# 01_-SensorAndActuator.net
KiCad netlist of a schematic drawn in Altium Designer
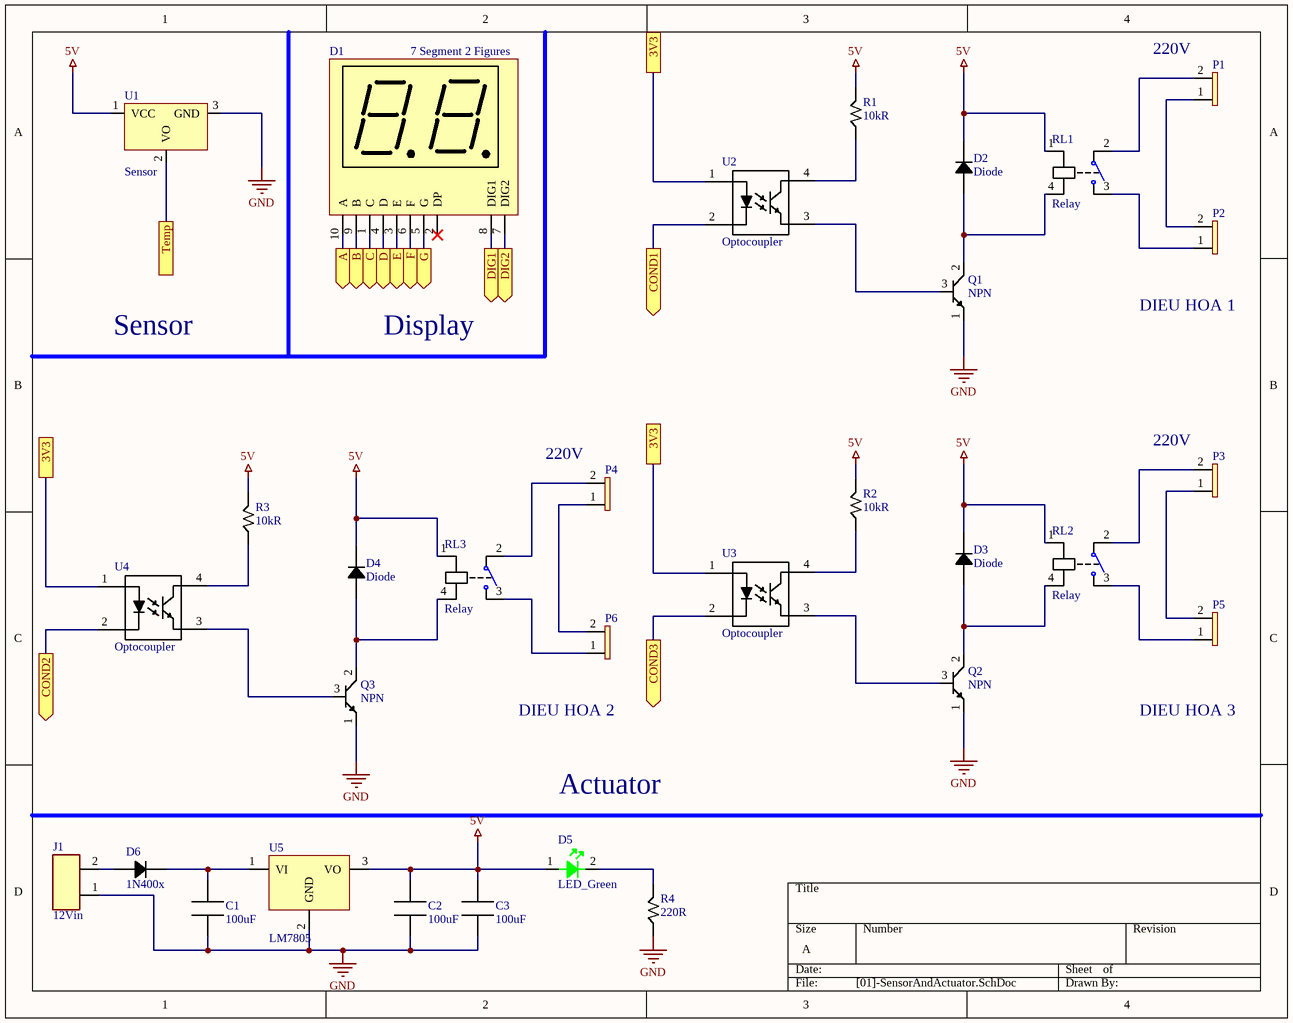
[diagram p0: [01]-SensorAndActuator.SchDoc]

(export (version "E")
  (design (tool "Eeschema 10.0.6"))
  (components
    (comp (ref "C1")
      (value "100uF")
      (footprint "Altium Lib:CAPC0805")
      (description "Capacitor_Non_Polar")
      (libsource (lib "Altium Lib") (part "Capacitor Non Polar"))
    )
    (comp (ref "C2")
      (value "100uF")
      (footprint "Altium Lib:CAPC0805")
      (description "Capacitor_Non_Polar")
      (libsource (lib "Altium Lib") (part "Capacitor Non Polar"))
    )
    (comp (ref "C3")
      (value "100uF")
      (footprint "Altium Lib:CAPC0805")
      (description "Capacitor_Non_Polar")
      (libsource (lib "Altium Lib") (part "Capacitor Non Polar"))
    )
    (comp (ref "D1")
      (value "7 Segment 2 Figures")
      (footprint "Altium Lib:5621BS")
      (libsource (lib "Altium Lib") (part "7 Segment 2 Figures"))
    )
    (comp (ref "D2")
      (value "Diode")
      (footprint "10A10")
      (description "Diode 10A")
      (libsource (lib "Altium Lib") (part "10A10"))
    )
    (comp (ref "D3")
      (value "Diode")
      (footprint "10A10")
      (description "Diode 10A")
      (libsource (lib "Altium Lib") (part "10A10"))
    )
    (comp (ref "D4")
      (value "Diode")
      (footprint "10A10")
      (description "Diode 10A")
      (libsource (lib "Altium Lib") (part "10A10"))
    )
    (comp (ref "D5")
      (value "LED_Green")
      (footprint "LED SMD 0805")
      (libsource (lib "Altium Lib") (part "LED_Green"))
    )
    (comp (ref "D6")
      (value "1N400x")
      (footprint "Altium Lib:1N400x")
      (description "1A - 1kV")
      (libsource (lib "Altium Lib") (part "Diode 1N4007"))
    )
    (comp (ref "J1")
      (value "12Vin")
      (footprint "Altium Lib:domino_2_pin")
      (description "2 Pins, 5.08mm")
      (libsource (lib "Altium Lib") (part "Domino 2 Pin"))
    )
    (comp (ref "P1")
      (value "Header 1*2 Pins")
      (footprint "HDR_M_2_PINS_2.54")
      (libsource (lib "Altium Lib") (part "Header 1x2 Pins"))
    )
    (comp (ref "P2")
      (value "Header 1*2 Pins")
      (footprint "HDR_M_2_PINS_2.54")
      (libsource (lib "Altium Lib") (part "Header 1x2 Pins"))
    )
    (comp (ref "P3")
      (value "Header 1*2 Pins")
      (footprint "HDR_M_2_PINS_2.54")
      (libsource (lib "Altium Lib") (part "Header 1x2 Pins"))
    )
    (comp (ref "P4")
      (value "Header 1*2 Pins")
      (footprint "HDR_M_2_PINS_2.54")
      (libsource (lib "Altium Lib") (part "Header 1x2 Pins"))
    )
    (comp (ref "P5")
      (value "Header 1*2 Pins")
      (footprint "HDR_M_2_PINS_2.54")
      (libsource (lib "Altium Lib") (part "Header 1x2 Pins"))
    )
    (comp (ref "P6")
      (value "Header 1*2 Pins")
      (footprint "HDR_M_2_PINS_2.54")
      (libsource (lib "Altium Lib") (part "Header 1x2 Pins"))
    )
    (comp (ref "Q1")
      (value "NPN")
      (footprint "to-92")
      (description "Transistor NPN")
      (libsource (lib "Altium Lib") (part "2SC1815"))
    )
    (comp (ref "Q2")
      (value "NPN")
      (footprint "to-92")
      (description "Transistor NPN")
      (libsource (lib "Altium Lib") (part "2SC1815"))
    )
    (comp (ref "Q3")
      (value "NPN")
      (footprint "to-92")
      (description "Transistor NPN")
      (libsource (lib "Altium Lib") (part "2SC1815"))
    )
    (comp (ref "R1")
      (value "10kR")
      (footprint "Altium Lib:RESC0805")
      (description "Resistor_TH_1/4W")
      (libsource (lib "Altium Lib") (part "Resistor"))
    )
    (comp (ref "R2")
      (value "10kR")
      (footprint "Altium Lib:RESC0805")
      (description "Resistor_TH_1/4W")
      (libsource (lib "Altium Lib") (part "Resistor"))
    )
    (comp (ref "R3")
      (value "10kR")
      (footprint "Altium Lib:RESC0805")
      (description "Resistor_TH_1/4W")
      (libsource (lib "Altium Lib") (part "Resistor"))
    )
    (comp (ref "R4")
      (value "220R")
      (footprint "Altium Lib:RESC0805")
      (description "Resistor_TH_1/4W")
      (libsource (lib "Altium Lib") (part "Resistor"))
    )
    (comp (ref "RL1")
      (value "Relay")
      (footprint "Relay G5NB")
      (description "4 Pins")
      (libsource (lib "Altium Lib") (part "Relay G5NB"))
    )
    (comp (ref "RL2")
      (value "Relay")
      (footprint "Relay G5NB")
      (description "4 Pins")
      (libsource (lib "Altium Lib") (part "Relay G5NB"))
    )
    (comp (ref "RL3")
      (value "Relay")
      (footprint "Relay G5NB")
      (description "4 Pins")
      (libsource (lib "Altium Lib") (part "Relay G5NB"))
    )
    (comp (ref "U1")
      (value "Sensor")
      (footprint "to-92")
      (description "Temperature sensor")
      (libsource (lib "Altium Lib") (part "LM35"))
    )
    (comp (ref "U2")
      (value "Optocoupler")
      (footprint "DIP 4")
      (description "Opto")
      (libsource (lib "Altium Lib") (part "Optocoupler"))
    )
    (comp (ref "U3")
      (value "Optocoupler")
      (footprint "DIP 4")
      (description "Opto")
      (libsource (lib "Altium Lib") (part "Optocoupler"))
    )
    (comp (ref "U4")
      (value "Optocoupler")
      (footprint "DIP 4")
      (description "Opto")
      (libsource (lib "Altium Lib") (part "Optocoupler"))
    )
    (comp (ref "U5")
      (value "LM7805")
      (footprint "Altium Lib:LM7805")
      (description "5V, 1A")
      (libsource (lib "Altium Lib") (part "LM7805"))
    )
  )
  (nets
    (net (code "1") (name "/3V3") (class "Default")
      (node (ref "U2") (pin "1") (pinfunction "Anode_1") (pintype "passive"))
      (node (ref "U3") (pin "1") (pinfunction "Anode_1") (pintype "passive"))
      (node (ref "U4") (pin "1") (pinfunction "Anode_1") (pintype "passive"))
    )
    (net (code "2") (name "/A") (class "Default")
      (node (ref "D1") (pin "10") (pinfunction "A_10") (pintype "passive"))
    )
    (net (code "3") (name "/B") (class "Default")
      (node (ref "D1") (pin "9") (pinfunction "B_9") (pintype "passive"))
    )
    (net (code "4") (name "/C") (class "Default")
      (node (ref "D1") (pin "1") (pinfunction "C_1") (pintype "passive"))
    )
    (net (code "5") (name "/COND1") (class "Default")
      (node (ref "U2") (pin "2") (pinfunction "Cathode_2") (pintype "passive"))
    )
    (net (code "6") (name "/COND2") (class "Default")
      (node (ref "U4") (pin "2") (pinfunction "Cathode_2") (pintype "passive"))
    )
    (net (code "7") (name "/COND3") (class "Default")
      (node (ref "U3") (pin "2") (pinfunction "Cathode_2") (pintype "passive"))
    )
    (net (code "8") (name "/D") (class "Default")
      (node (ref "D1") (pin "4") (pinfunction "D_4") (pintype "passive"))
    )
    (net (code "9") (name "/DIG1") (class "Default")
      (node (ref "D1") (pin "8") (pinfunction "DIG1_8") (pintype "passive"))
    )
    (net (code "10") (name "/DIG2") (class "Default")
      (node (ref "D1") (pin "7") (pinfunction "DIG2_7") (pintype "passive"))
    )
    (net (code "11") (name "/E") (class "Default")
      (node (ref "D1") (pin "3") (pinfunction "E_3") (pintype "passive"))
    )
    (net (code "12") (name "/F") (class "Default")
      (node (ref "D1") (pin "6") (pinfunction "F_6") (pintype "passive"))
    )
    (net (code "13") (name "/G") (class "Default")
      (node (ref "D1") (pin "5") (pinfunction "G_5") (pintype "passive"))
    )
    (net (code "14") (name "/Temp") (class "Default")
      (node (ref "U1") (pin "2") (pinfunction "VO_2") (pintype "passive"))
    )
    (net (code "15") (name "5V") (class "Default")
      (node (ref "C2") (pin "2") (pinfunction "2_2") (pintype "passive"))
      (node (ref "C3") (pin "2") (pinfunction "2_2") (pintype "passive"))
      (node (ref "D2") (pin "2") (pinfunction "2_2") (pintype "passive"))
      (node (ref "D3") (pin "2") (pinfunction "2_2") (pintype "passive"))
      (node (ref "D4") (pin "2") (pinfunction "2_2") (pintype "passive"))
      (node (ref "D5") (pin "1") (pinfunction "1_1") (pintype "passive"))
      (node (ref "R1") (pin "2") (pinfunction "2_2") (pintype "passive"))
      (node (ref "R2") (pin "2") (pinfunction "2_2") (pintype "passive"))
      (node (ref "R3") (pin "2") (pinfunction "2_2") (pintype "passive"))
      (node (ref "RL1") (pin "1") (pinfunction "1_1") (pintype "passive"))
      (node (ref "RL2") (pin "1") (pinfunction "1_1") (pintype "passive"))
      (node (ref "RL3") (pin "1") (pinfunction "1_1") (pintype "passive"))
      (node (ref "U1") (pin "1") (pinfunction "VCC_1") (pintype "passive"))
      (node (ref "U5") (pin "3") (pinfunction "VO_3") (pintype "passive"))
    )
    (net (code "16") (name "GND") (class "Default")
      (node (ref "C1") (pin "1") (pinfunction "1_1") (pintype "passive"))
      (node (ref "C2") (pin "1") (pinfunction "1_1") (pintype "passive"))
      (node (ref "C3") (pin "1") (pinfunction "1_1") (pintype "passive"))
      (node (ref "J1") (pin "1") (pinfunction "1_1") (pintype "passive"))
      (node (ref "Q1") (pin "1") (pinfunction "Emitter_1") (pintype "passive"))
      (node (ref "Q2") (pin "1") (pinfunction "Emitter_1") (pintype "passive"))
      (node (ref "Q3") (pin "1") (pinfunction "Emitter_1") (pintype "passive"))
      (node (ref "R4") (pin "1") (pinfunction "1_1") (pintype "passive"))
      (node (ref "U1") (pin "3") (pinfunction "GND_3") (pintype "passive"))
      (node (ref "U5") (pin "2") (pinfunction "GND_2") (pintype "passive"))
    )
    (net (code "17") (name "Net-(D5-Pad2)") (class "Default")
      (node (ref "D5") (pin "2") (pinfunction "2_2") (pintype "passive"))
      (node (ref "R4") (pin "2") (pinfunction "2_2") (pintype "passive"))
    )
    (net (code "18") (name "Net-(D6-Pad1)") (class "Default")
      (node (ref "D6") (pin "1") (pinfunction "1_1") (pintype "passive"))
      (node (ref "J1") (pin "2") (pinfunction "2_2") (pintype "passive"))
    )
    (net (code "19") (name "Net-(P1-Pad1)") (class "Default")
      (node (ref "P1") (pin "1") (pinfunction "1_1") (pintype "passive"))
      (node (ref "P2") (pin "2") (pinfunction "2_2") (pintype "passive"))
    )
    (net (code "20") (name "Net-(P1-Pad2)") (class "Default")
      (node (ref "P1") (pin "2") (pinfunction "2_2") (pintype "passive"))
      (node (ref "RL1") (pin "2") (pinfunction "2_2") (pintype "passive"))
    )
    (net (code "21") (name "Net-(P2-Pad1)") (class "Default")
      (node (ref "P2") (pin "1") (pinfunction "1_1") (pintype "passive"))
      (node (ref "RL1") (pin "3") (pinfunction "3_3") (pintype "passive"))
    )
    (net (code "22") (name "Net-(P3-Pad1)") (class "Default")
      (node (ref "P3") (pin "1") (pinfunction "1_1") (pintype "passive"))
      (node (ref "P5") (pin "2") (pinfunction "2_2") (pintype "passive"))
    )
    (net (code "23") (name "Net-(P3-Pad2)") (class "Default")
      (node (ref "P3") (pin "2") (pinfunction "2_2") (pintype "passive"))
      (node (ref "RL2") (pin "2") (pinfunction "2_2") (pintype "passive"))
    )
    (net (code "24") (name "Net-(P4-Pad1)") (class "Default")
      (node (ref "P4") (pin "1") (pinfunction "1_1") (pintype "passive"))
      (node (ref "P6") (pin "2") (pinfunction "2_2") (pintype "passive"))
    )
    (net (code "25") (name "Net-(P4-Pad2)") (class "Default")
      (node (ref "P4") (pin "2") (pinfunction "2_2") (pintype "passive"))
      (node (ref "RL3") (pin "2") (pinfunction "2_2") (pintype "passive"))
    )
    (net (code "26") (name "Net-(P5-Pad1)") (class "Default")
      (node (ref "P5") (pin "1") (pinfunction "1_1") (pintype "passive"))
      (node (ref "RL2") (pin "3") (pinfunction "3_3") (pintype "passive"))
    )
    (net (code "27") (name "Net-(P6-Pad1)") (class "Default")
      (node (ref "P6") (pin "1") (pinfunction "1_1") (pintype "passive"))
      (node (ref "RL3") (pin "3") (pinfunction "3_3") (pintype "passive"))
    )
    (net (code "28") (name "Net-(Q1-Base)") (class "Default")
      (node (ref "Q1") (pin "3") (pinfunction "Base_3") (pintype "passive"))
      (node (ref "U2") (pin "3") (pinfunction "Emitter_3") (pintype "passive"))
    )
    (net (code "29") (name "Net-(Q1-Collector)") (class "Default")
      (node (ref "D2") (pin "1") (pinfunction "1_1") (pintype "passive"))
      (node (ref "Q1") (pin "2") (pinfunction "Collector_2") (pintype "passive"))
      (node (ref "RL1") (pin "4") (pinfunction "4_4") (pintype "passive"))
    )
    (net (code "30") (name "Net-(Q2-Base)") (class "Default")
      (node (ref "Q2") (pin "3") (pinfunction "Base_3") (pintype "passive"))
      (node (ref "U3") (pin "3") (pinfunction "Emitter_3") (pintype "passive"))
    )
    (net (code "31") (name "Net-(Q2-Collector)") (class "Default")
      (node (ref "D3") (pin "1") (pinfunction "1_1") (pintype "passive"))
      (node (ref "Q2") (pin "2") (pinfunction "Collector_2") (pintype "passive"))
      (node (ref "RL2") (pin "4") (pinfunction "4_4") (pintype "passive"))
    )
    (net (code "32") (name "Net-(Q3-Base)") (class "Default")
      (node (ref "Q3") (pin "3") (pinfunction "Base_3") (pintype "passive"))
      (node (ref "U4") (pin "3") (pinfunction "Emitter_3") (pintype "passive"))
    )
    (net (code "33") (name "Net-(Q3-Collector)") (class "Default")
      (node (ref "D4") (pin "1") (pinfunction "1_1") (pintype "passive"))
      (node (ref "Q3") (pin "2") (pinfunction "Collector_2") (pintype "passive"))
      (node (ref "RL3") (pin "4") (pinfunction "4_4") (pintype "passive"))
    )
    (net (code "34") (name "Net-(U2-Collector)") (class "Default")
      (node (ref "R1") (pin "1") (pinfunction "1_1") (pintype "passive"))
      (node (ref "U2") (pin "4") (pinfunction "Collector_4") (pintype "passive"))
    )
    (net (code "35") (name "Net-(U3-Collector)") (class "Default")
      (node (ref "R2") (pin "1") (pinfunction "1_1") (pintype "passive"))
      (node (ref "U3") (pin "4") (pinfunction "Collector_4") (pintype "passive"))
    )
    (net (code "36") (name "Net-(U4-Collector)") (class "Default")
      (node (ref "R3") (pin "1") (pinfunction "1_1") (pintype "passive"))
      (node (ref "U4") (pin "4") (pinfunction "Collector_4") (pintype "passive"))
    )
    (net (code "37") (name "Net-(U5-VI)") (class "Default")
      (node (ref "C1") (pin "2") (pinfunction "2_2") (pintype "passive"))
      (node (ref "D6") (pin "2") (pinfunction "2_2") (pintype "passive"))
      (node (ref "U5") (pin "1") (pinfunction "VI_1") (pintype "passive"))
    )
    (net (code "38") (name "unconnected-(D1-DP-Pad2)") (class "Default")
      (node (ref "D1") (pin "2") (pinfunction "DP_2") (pintype "passive+no_connect"))
    )
  )
)
